# PCB_1.net
KiCad netlist of a schematic drawn in EAGLE
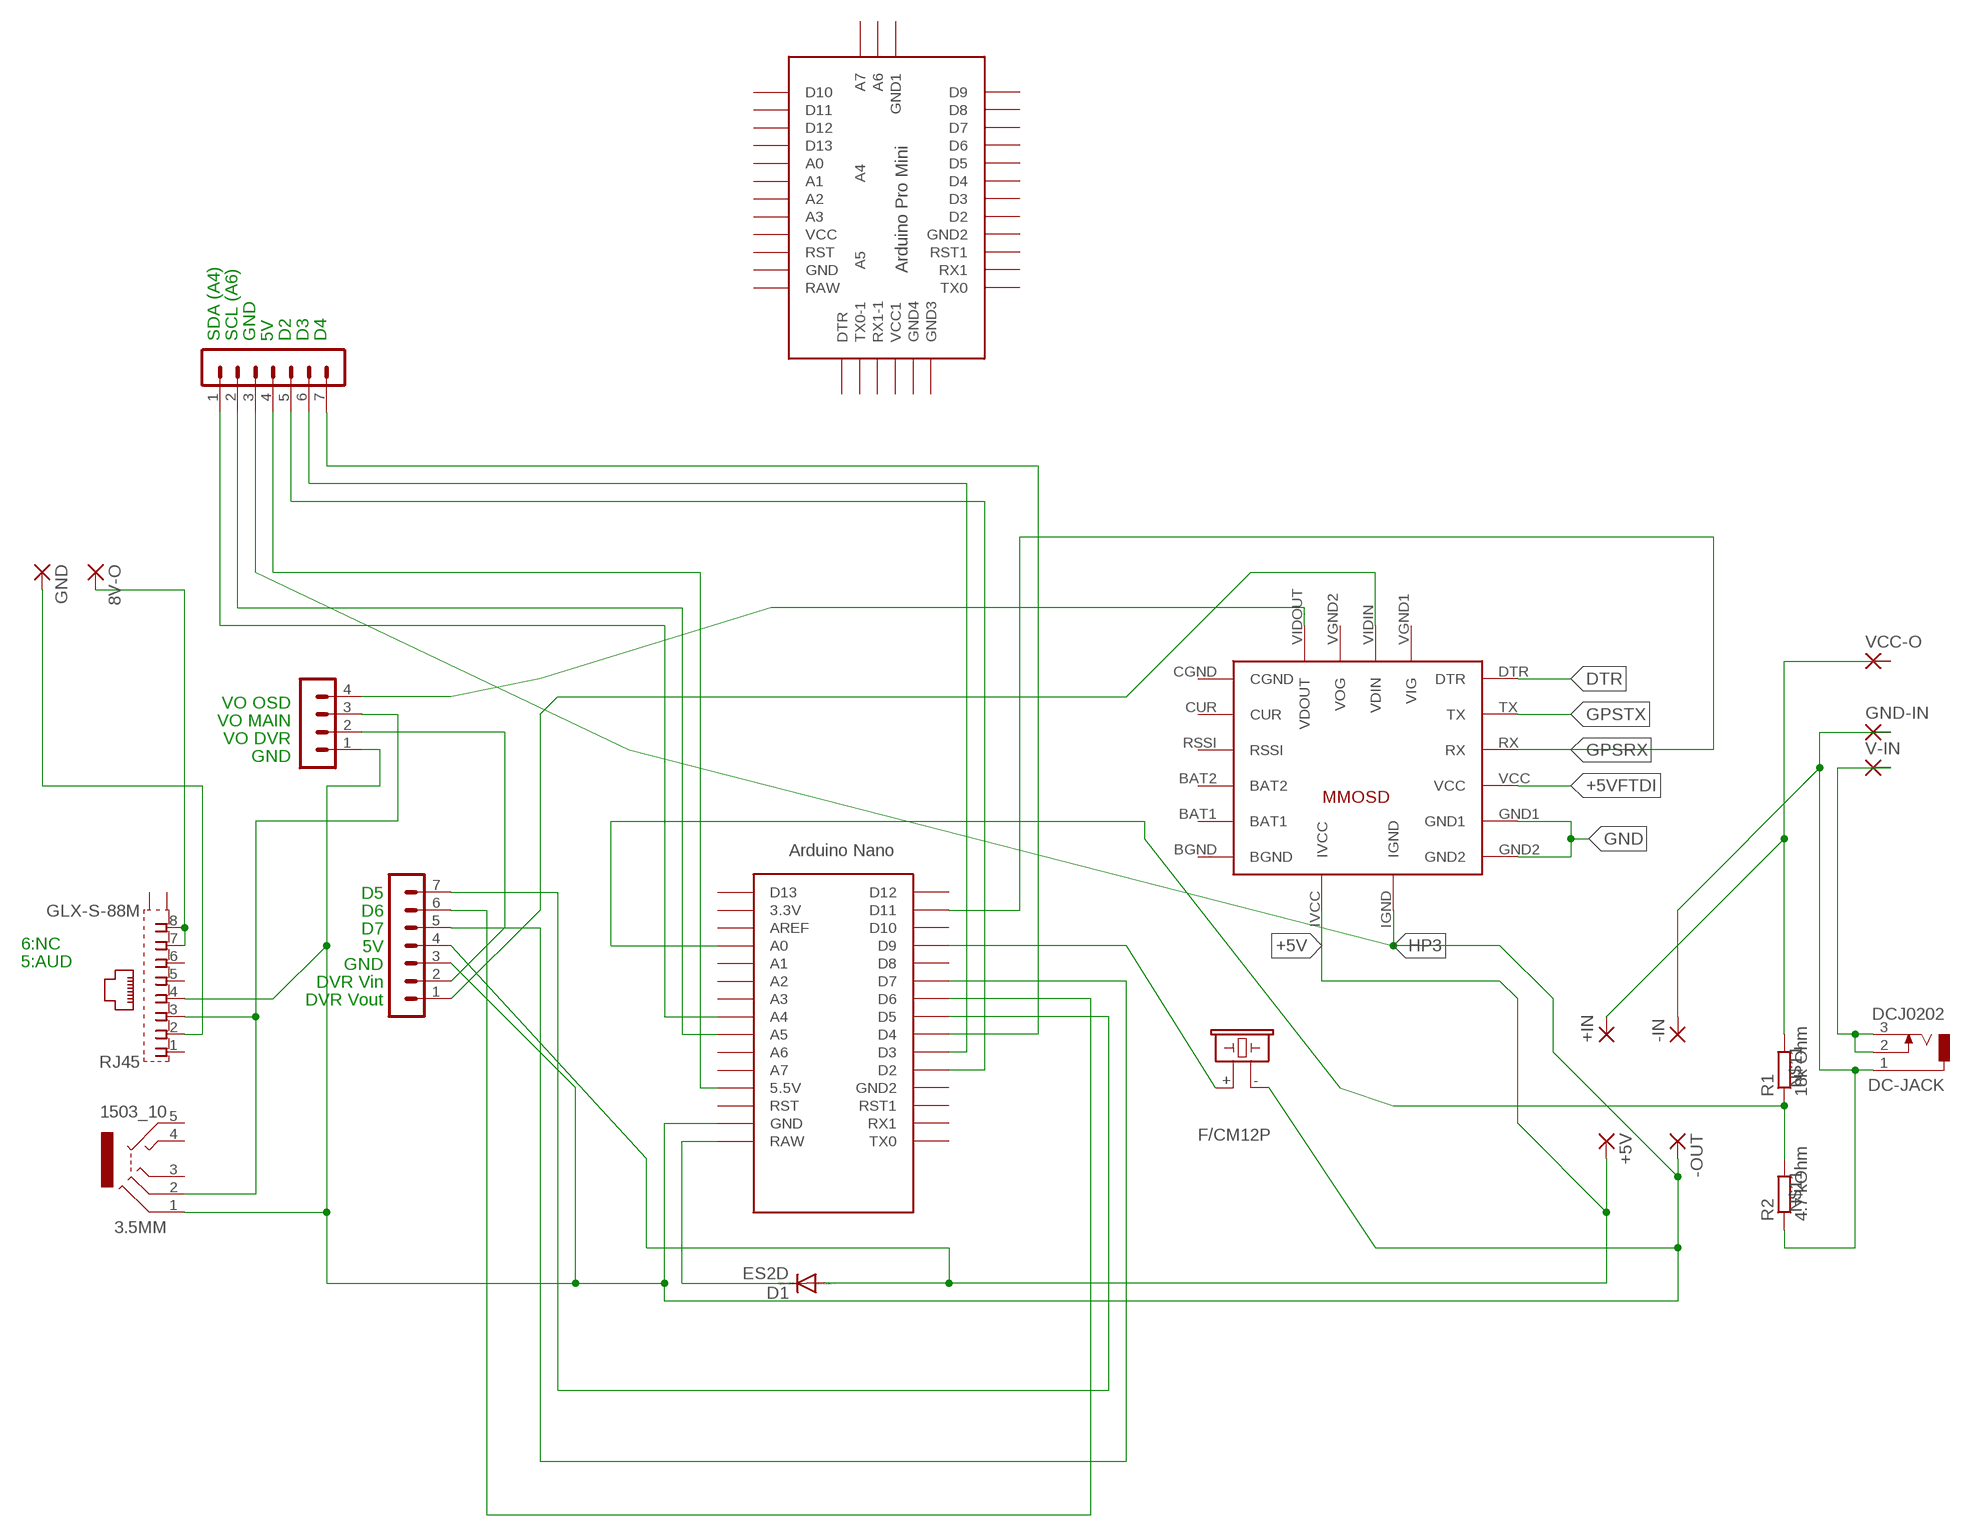
[diagram p0: schematic, sheet 1]

(export (version "E")
  (design (tool "Eeschema 10.0.6"))
  (components
    (comp (ref "+5V")
      (value "SMD2")
      (footprint "eagle-import:SMD1,27-2,54")
      (libsource (lib "eagle-import") (part "SMD2"))
    )
    (comp (ref "+IN")
      (value "SMD2")
      (footprint "eagle-import:SMD1,27-2,54")
      (libsource (lib "eagle-import") (part "SMD2"))
    )
    (comp (ref "-IN")
      (value "SMD2")
      (footprint "eagle-import:SMD1,27-2,54")
      (libsource (lib "eagle-import") (part "SMD2"))
    )
    (comp (ref "-OUT")
      (value "SMD2")
      (footprint "eagle-import:SMD1,27-2,54")
      (libsource (lib "eagle-import") (part "SMD2"))
    )
    (comp (ref "3.5MM")
      (value "1503_10")
      (footprint "eagle-import:1503_10")
      (libsource (lib "eagle-import") (part "1503_10"))
    )
    (comp (ref "8V-O")
      (value "2,54/1,1")
      (footprint "eagle-import:2,54_1,1")
      (libsource (lib "eagle-import") (part "2,54/1,1"))
    )
    (comp (ref "ADRUINO-NANO")
      (value "NANOB")
      (footprint "eagle-import:NANO")
      (libsource (lib "eagle-import") (part "NANOB"))
    )
    (comp (ref "BUZZ")
      (value "F/CM12P")
      (footprint "eagle-import:F_CM12P")
      (fields (field (name "SPICEPREFIX") "X"))
      (libsource (lib "eagle-import") (part "F/CM12P"))
    )
    (comp (ref "D1")
      (value "ES2D")
      (footprint "eagle-import:SMB")
      (libsource (lib "eagle-import") (part "ES2D"))
    )
    (comp (ref "DC-JACK")
      (value "DCJ0202")
      (footprint "eagle-import:DCJ0202")
      (libsource (lib "eagle-import") (part "DCJ0202"))
    )
    (comp (ref "GND")
      (value "2,54/1,1")
      (footprint "eagle-import:2,54_1,1")
      (libsource (lib "eagle-import") (part "2,54/1,1"))
    )
    (comp (ref "GND-IN")
      (value "2,54/1,1")
      (footprint "eagle-import:2,54_1,1")
      (libsource (lib "eagle-import") (part "2,54/1,1"))
    )
    (comp (ref "IO1")
      (value "MA07-1")
      (footprint "eagle-import:MA07-1")
      (libsource (lib "eagle-import") (part "MA07-1"))
    )
    (comp (ref "IO2")
      (value "MA07-1")
      (footprint "eagle-import:MA07-1")
      (libsource (lib "eagle-import") (part "MA07-1"))
    )
    (comp (ref "IO3")
      (value "MA04-1")
      (footprint "eagle-import:MA04-1")
      (libsource (lib "eagle-import") (part "MA04-1"))
    )
    (comp (ref "MINIMOSD")
      (value "MICROMINIMOSDPWR")
      (footprint "eagle-import:MMOSDNVDVID")
      (libsource (lib "eagle-import") (part "MICROMINIMOSDPWR"))
    )
    (comp (ref "R1")
      (value "18k Ohm")
      (footprint "eagle-import:M1206")
      (libsource (lib "eagle-import") (part "R-EU_M1206"))
    )
    (comp (ref "R2")
      (value "4.7 kOhm")
      (footprint "eagle-import:M1206")
      (libsource (lib "eagle-import") (part "R-EU_M1206"))
    )
    (comp (ref "RJ45")
      (value "GLX-S-88M")
      (footprint "eagle-import:GLX-S-88M")
      (libsource (lib "eagle-import") (part "GLX-S-88M"))
    )
    (comp (ref "U$1")
      (value "ABK-PRO-MINI")
      (footprint "eagle-import:ABK-PRO-MINI")
      (libsource (lib "eagle-import") (part "ABK-PRO-MINI"))
    )
    (comp (ref "V-IN")
      (value "2,54/1,1")
      (footprint "eagle-import:2,54_1,1")
      (libsource (lib "eagle-import") (part "2,54/1,1"))
    )
    (comp (ref "VCC-O")
      (value "2,54/1,1")
      (footprint "eagle-import:2,54_1,1")
      (libsource (lib "eagle-import") (part "2,54/1,1"))
    )
  )
  (nets
    (net (code "1") (name "+5V") (class "Default")
      (node (ref "+5V") (pin "1") (pinfunction "P_1") (pintype "passive"))
      (node (ref "D1") (pin "A") (pinfunction "A_A") (pintype "passive"))
      (node (ref "IO1") (pin "4") (pinfunction "4_4") (pintype "passive"))
      (node (ref "MINIMOSD") (pin "IVCC") (pinfunction "IVCC_IVCC") (pintype "power_in"))
    )
    (net (code "2") (name "+5VFTDI") (class "Default")
      (node (ref "MINIMOSD") (pin "VCC") (pinfunction "VCC_VCC") (pintype "power_in"))
    )
    (net (code "3") (name "/BAT1") (class "Default")
      (node (ref "MINIMOSD") (pin "BAT1") (pinfunction "BAT1_BAT1") (pintype "power_in"))
    )
    (net (code "4") (name "/BAT2") (class "Default")
      (node (ref "MINIMOSD") (pin "BAT2") (pinfunction "BAT2_BAT2") (pintype "power_in"))
    )
    (net (code "5") (name "/BGND") (class "Default")
      (node (ref "MINIMOSD") (pin "BGND") (pinfunction "BGND_BGND") (pintype "power_in"))
    )
    (net (code "6") (name "/CGND") (class "Default")
      (node (ref "MINIMOSD") (pin "CGND") (pinfunction "CGND_CGND") (pintype "power_in"))
    )
    (net (code "7") (name "/N$11") (class "Default")
      (node (ref "-IN") (pin "1") (pinfunction "P_1") (pintype "passive"))
      (node (ref "DC-JACK") (pin "1") (pinfunction "1_1") (pintype "passive"))
      (node (ref "GND-IN") (pin "1") (pinfunction "P_1") (pintype "passive"))
      (node (ref "R2") (pin "1") (pinfunction "1_1") (pintype "passive"))
    )
    (net (code "8") (name "DTR") (class "Default")
      (node (ref "MINIMOSD") (pin "DTR") (pinfunction "DTR_DTR") (pintype "bidirectional"))
    )
    (net (code "9") (name "GND") (class "Default")
      (node (ref "MINIMOSD") (pin "GND1") (pinfunction "GND1_GND1") (pintype "power_in"))
      (node (ref "MINIMOSD") (pin "GND2") (pinfunction "GND2_GND2") (pintype "power_in"))
    )
    (net (code "10") (name "GPSRX") (class "Default")
      (node (ref "ADRUINO-NANO") (pin "D11") (pinfunction "D11_D11") (pintype "bidirectional"))
      (node (ref "MINIMOSD") (pin "RX") (pinfunction "RX_RX") (pintype "input"))
    )
    (net (code "11") (name "GPSTX") (class "Default")
      (node (ref "MINIMOSD") (pin "TX") (pinfunction "TX_TX") (pintype "output"))
    )
    (net (code "12") (name "HP3") (class "Default")
      (node (ref "-OUT") (pin "1") (pinfunction "P_1") (pintype "passive"))
      (node (ref "3.5MM") (pin "1") (pinfunction "1_1") (pintype "passive"))
      (node (ref "ADRUINO-NANO") (pin "GND") (pinfunction "GND_GND") (pintype "bidirectional"))
      (node (ref "BUZZ") (pin "-") (pinfunction "2_-") (pintype "passive"))
      (node (ref "IO1") (pin "3") (pinfunction "3_3") (pintype "passive"))
      (node (ref "IO2") (pin "3") (pinfunction "3_3") (pintype "passive"))
      (node (ref "IO3") (pin "1") (pinfunction "1_1") (pintype "passive"))
      (node (ref "MINIMOSD") (pin "IGND") (pinfunction "IGND_IGND") (pintype "power_in"))
      (node (ref "RJ45") (pin "4") (pinfunction "4_4") (pintype "passive"))
    )
    (net (code "13") (name "Net-(+IN-P)") (class "Default")
      (node (ref "+IN") (pin "1") (pinfunction "P_1") (pintype "passive"))
      (node (ref "R1") (pin "2") (pinfunction "2_2") (pintype "passive"))
      (node (ref "VCC-O") (pin "1") (pinfunction "P_1") (pintype "passive"))
    )
    (net (code "14") (name "Net-(3.5MM-Pad2)") (class "Default")
      (node (ref "3.5MM") (pin "2") (pinfunction "2_2") (pintype "passive"))
      (node (ref "IO3") (pin "3") (pinfunction "3_3") (pintype "passive"))
      (node (ref "RJ45") (pin "3") (pinfunction "3_3") (pintype "passive"))
    )
    (net (code "15") (name "Net-(8V-O-P)") (class "Default")
      (node (ref "8V-O") (pin "1") (pinfunction "P_1") (pintype "passive"))
      (node (ref "RJ45") (pin "7") (pinfunction "7_7") (pintype "passive"))
      (node (ref "RJ45") (pin "8") (pinfunction "8_8") (pintype "passive"))
    )
    (net (code "16") (name "Net-(ADRUINO-NANO-5.5V)") (class "Default")
      (node (ref "ADRUINO-NANO") (pin "5V") (pinfunction "5.5V_5V") (pintype "bidirectional"))
      (node (ref "IO2") (pin "4") (pinfunction "4_4") (pintype "passive"))
    )
    (net (code "17") (name "Net-(ADRUINO-NANO-PadA0)") (class "Default")
      (node (ref "ADRUINO-NANO") (pin "A0") (pinfunction "A0_A0") (pintype "bidirectional"))
      (node (ref "R1") (pin "1") (pinfunction "1_1") (pintype "passive"))
      (node (ref "R2") (pin "2") (pinfunction "2_2") (pintype "passive"))
    )
    (net (code "18") (name "Net-(ADRUINO-NANO-PadA4)") (class "Default")
      (node (ref "ADRUINO-NANO") (pin "A4") (pinfunction "A4_A4") (pintype "bidirectional"))
      (node (ref "IO2") (pin "1") (pinfunction "1_1") (pintype "passive"))
    )
    (net (code "19") (name "Net-(ADRUINO-NANO-PadA5)") (class "Default")
      (node (ref "ADRUINO-NANO") (pin "A5") (pinfunction "A5_A5") (pintype "bidirectional"))
      (node (ref "IO2") (pin "2") (pinfunction "2_2") (pintype "passive"))
    )
    (net (code "20") (name "Net-(ADRUINO-NANO-PadD2)") (class "Default")
      (node (ref "ADRUINO-NANO") (pin "D2") (pinfunction "D2_D2") (pintype "bidirectional"))
      (node (ref "IO2") (pin "5") (pinfunction "5_5") (pintype "passive"))
    )
    (net (code "21") (name "Net-(ADRUINO-NANO-PadD3)") (class "Default")
      (node (ref "ADRUINO-NANO") (pin "D3") (pinfunction "D3_D3") (pintype "bidirectional"))
      (node (ref "IO2") (pin "6") (pinfunction "6_6") (pintype "passive"))
    )
    (net (code "22") (name "Net-(ADRUINO-NANO-PadD4)") (class "Default")
      (node (ref "ADRUINO-NANO") (pin "D4") (pinfunction "D4_D4") (pintype "bidirectional"))
      (node (ref "IO2") (pin "7") (pinfunction "7_7") (pintype "passive"))
    )
    (net (code "23") (name "Net-(ADRUINO-NANO-PadD5)") (class "Default")
      (node (ref "ADRUINO-NANO") (pin "D5") (pinfunction "D5_D5") (pintype "bidirectional"))
      (node (ref "IO1") (pin "7") (pinfunction "7_7") (pintype "passive"))
    )
    (net (code "24") (name "Net-(ADRUINO-NANO-PadD6)") (class "Default")
      (node (ref "ADRUINO-NANO") (pin "D6") (pinfunction "D6_D6") (pintype "bidirectional"))
      (node (ref "IO1") (pin "6") (pinfunction "6_6") (pintype "passive"))
    )
    (net (code "25") (name "Net-(ADRUINO-NANO-PadD7)") (class "Default")
      (node (ref "ADRUINO-NANO") (pin "D7") (pinfunction "D7_D7") (pintype "bidirectional"))
      (node (ref "IO1") (pin "5") (pinfunction "5_5") (pintype "passive"))
    )
    (net (code "26") (name "Net-(ADRUINO-NANO-PadRAW)") (class "Default")
      (node (ref "ADRUINO-NANO") (pin "RAW") (pinfunction "RAW_RAW") (pintype "bidirectional"))
      (node (ref "D1") (pin "C") (pinfunction "C_C") (pintype "passive"))
    )
    (net (code "27") (name "Net-(BUZZ-1)") (class "Default")
      (node (ref "ADRUINO-NANO") (pin "D9") (pinfunction "D9_D9") (pintype "bidirectional"))
      (node (ref "BUZZ") (pin "+") (pinfunction "1_+") (pintype "passive"))
    )
    (net (code "28") (name "Net-(GND-P)") (class "Default")
      (node (ref "GND") (pin "1") (pinfunction "P_1") (pintype "passive"))
      (node (ref "RJ45") (pin "2") (pinfunction "2_2") (pintype "passive"))
    )
    (net (code "29") (name "Net-(IO1-Pad2)") (class "Default")
      (node (ref "IO1") (pin "2") (pinfunction "2_2") (pintype "passive"))
      (node (ref "IO3") (pin "2") (pinfunction "2_2") (pintype "passive"))
    )
    (net (code "30") (name "Net-(MINIMOSD-VDIN)") (class "Default")
      (node (ref "IO1") (pin "1") (pinfunction "1_1") (pintype "passive"))
      (node (ref "MINIMOSD") (pin "VIDIN") (pinfunction "VDIN_VIDIN") (pintype "input"))
    )
    (net (code "31") (name "Net-(MINIMOSD-VDOUT)") (class "Default")
      (node (ref "IO3") (pin "4") (pinfunction "4_4") (pintype "passive"))
      (node (ref "MINIMOSD") (pin "VIDOUT") (pinfunction "VDOUT_VIDOUT") (pintype "output"))
    )
    (net (code "32") (name "Net-(V-IN-P)") (class "Default")
      (node (ref "DC-JACK") (pin "2") (pinfunction "2_2") (pintype "passive"))
      (node (ref "DC-JACK") (pin "3") (pinfunction "3_3") (pintype "passive"))
      (node (ref "V-IN") (pin "1") (pinfunction "P_1") (pintype "passive"))
    )
    (net (code "33") (name "unconnected-(3.5MM-Pad3)") (class "Default")
      (node (ref "3.5MM") (pin "3") (pinfunction "3_3") (pintype "passive"))
    )
    (net (code "34") (name "unconnected-(3.5MM-Pad4)") (class "Default")
      (node (ref "3.5MM") (pin "4") (pinfunction "4_4") (pintype "passive"))
    )
    (net (code "35") (name "unconnected-(3.5MM-Pad5)") (class "Default")
      (node (ref "3.5MM") (pin "5") (pinfunction "5_5") (pintype "passive"))
    )
    (net (code "36") (name "unconnected-(ADRUINO-NANO-GND2-PadGND1)") (class "Default")
      (node (ref "ADRUINO-NANO") (pin "GND1") (pinfunction "GND2_GND1") (pintype "bidirectional"))
    )
    (net (code "37") (name "unconnected-(ADRUINO-NANO-Pad3.3V)") (class "Default")
      (node (ref "ADRUINO-NANO") (pin "3.3V") (pinfunction "3.3V_3.3V") (pintype "bidirectional"))
    )
    (net (code "38") (name "unconnected-(ADRUINO-NANO-PadA1)") (class "Default")
      (node (ref "ADRUINO-NANO") (pin "A1") (pinfunction "A1_A1") (pintype "bidirectional"))
    )
    (net (code "39") (name "unconnected-(ADRUINO-NANO-PadA2)") (class "Default")
      (node (ref "ADRUINO-NANO") (pin "A2") (pinfunction "A2_A2") (pintype "bidirectional"))
    )
    (net (code "40") (name "unconnected-(ADRUINO-NANO-PadA3)") (class "Default")
      (node (ref "ADRUINO-NANO") (pin "A3") (pinfunction "A3_A3") (pintype "bidirectional"))
    )
    (net (code "41") (name "unconnected-(ADRUINO-NANO-PadA6)") (class "Default")
      (node (ref "ADRUINO-NANO") (pin "A6") (pinfunction "A6_A6") (pintype "bidirectional"))
    )
    (net (code "42") (name "unconnected-(ADRUINO-NANO-PadA7)") (class "Default")
      (node (ref "ADRUINO-NANO") (pin "A7") (pinfunction "A7_A7") (pintype "bidirectional"))
    )
    (net (code "43") (name "unconnected-(ADRUINO-NANO-PadAREF)") (class "Default")
      (node (ref "ADRUINO-NANO") (pin "AREF") (pinfunction "AREF_AREF") (pintype "bidirectional"))
    )
    (net (code "44") (name "unconnected-(ADRUINO-NANO-PadD8)") (class "Default")
      (node (ref "ADRUINO-NANO") (pin "D8") (pinfunction "D8_D8") (pintype "bidirectional"))
    )
    (net (code "45") (name "unconnected-(ADRUINO-NANO-PadD10)") (class "Default")
      (node (ref "ADRUINO-NANO") (pin "D10") (pinfunction "D10_D10") (pintype "bidirectional"))
    )
    (net (code "46") (name "unconnected-(ADRUINO-NANO-PadD12)") (class "Default")
      (node (ref "ADRUINO-NANO") (pin "D12") (pinfunction "D12_D12") (pintype "bidirectional"))
    )
    (net (code "47") (name "unconnected-(ADRUINO-NANO-PadD13)") (class "Default")
      (node (ref "ADRUINO-NANO") (pin "D13") (pinfunction "D13_D13") (pintype "bidirectional"))
    )
    (net (code "48") (name "unconnected-(ADRUINO-NANO-PadRST)") (class "Default")
      (node (ref "ADRUINO-NANO") (pin "RST") (pinfunction "RST_RST") (pintype "bidirectional"))
    )
    (net (code "49") (name "unconnected-(ADRUINO-NANO-PadRST1)") (class "Default")
      (node (ref "ADRUINO-NANO") (pin "RST1") (pinfunction "RST1_RST1") (pintype "bidirectional"))
    )
    (net (code "50") (name "unconnected-(ADRUINO-NANO-PadRX1)") (class "Default")
      (node (ref "ADRUINO-NANO") (pin "RX1") (pinfunction "RX1_RX1") (pintype "bidirectional"))
    )
    (net (code "51") (name "unconnected-(ADRUINO-NANO-PadTX0)") (class "Default")
      (node (ref "ADRUINO-NANO") (pin "TX0") (pinfunction "TX0_TX0") (pintype "bidirectional"))
    )
    (net (code "52") (name "unconnected-(MINIMOSD-PadCUR)") (class "Default")
      (node (ref "MINIMOSD") (pin "CUR") (pinfunction "CUR_CUR") (pintype "bidirectional"))
    )
    (net (code "53") (name "unconnected-(MINIMOSD-PadRSSI)") (class "Default")
      (node (ref "MINIMOSD") (pin "RSSI") (pinfunction "RSSI_RSSI") (pintype "bidirectional"))
    )
    (net (code "54") (name "unconnected-(MINIMOSD-VIG-PadVGND1)") (class "Default")
      (node (ref "MINIMOSD") (pin "VGND1") (pinfunction "VIG_VGND1") (pintype "input"))
    )
    (net (code "55") (name "unconnected-(MINIMOSD-VOG-PadVGND2)") (class "Default")
      (node (ref "MINIMOSD") (pin "VGND2") (pinfunction "VOG_VGND2") (pintype "output"))
    )
    (net (code "56") (name "unconnected-(RJ45-Pad1)") (class "Default")
      (node (ref "RJ45") (pin "1") (pinfunction "1_1") (pintype "passive"))
    )
    (net (code "57") (name "unconnected-(RJ45-Pad5)") (class "Default")
      (node (ref "RJ45") (pin "5") (pinfunction "5_5") (pintype "passive"))
    )
    (net (code "58") (name "unconnected-(RJ45-Pad6)") (class "Default")
      (node (ref "RJ45") (pin "6") (pinfunction "6_6") (pintype "passive"))
    )
    (net (code "59") (name "unconnected-(RJ45-PadS1)") (class "Default")
      (node (ref "RJ45") (pin "S1") (pinfunction "S1_S1") (pintype "passive"))
    )
    (net (code "60") (name "unconnected-(RJ45-PadS2)") (class "Default")
      (node (ref "RJ45") (pin "S2") (pinfunction "S2_S2") (pintype "passive"))
    )
    (net (code "61") (name "unconnected-(U$1-GND1-PadGND4)") (class "Default")
      (node (ref "U$1") (pin "GND4") (pinfunction "GND1_GND4") (pintype "bidirectional"))
    )
    (net (code "62") (name "unconnected-(U$1-GND2-PadGND1)") (class "Default")
      (node (ref "U$1") (pin "GND1") (pinfunction "GND2_GND1") (pintype "bidirectional"))
    )
    (net (code "63") (name "unconnected-(U$1-GND3-PadGND2)") (class "Default")
      (node (ref "U$1") (pin "GND2") (pinfunction "GND3_GND2") (pintype "bidirectional"))
    )
    (net (code "64") (name "unconnected-(U$1-GND4-PadGND3)") (class "Default")
      (node (ref "U$1") (pin "GND3") (pinfunction "GND4_GND3") (pintype "bidirectional"))
    )
    (net (code "65") (name "unconnected-(U$1-PadA0)") (class "Default")
      (node (ref "U$1") (pin "A0") (pinfunction "A0_A0") (pintype "bidirectional"))
    )
    (net (code "66") (name "unconnected-(U$1-PadA1)") (class "Default")
      (node (ref "U$1") (pin "A1") (pinfunction "A1_A1") (pintype "bidirectional"))
    )
    (net (code "67") (name "unconnected-(U$1-PadA2)") (class "Default")
      (node (ref "U$1") (pin "A2") (pinfunction "A2_A2") (pintype "bidirectional"))
    )
    (net (code "68") (name "unconnected-(U$1-PadA3)") (class "Default")
      (node (ref "U$1") (pin "A3") (pinfunction "A3_A3") (pintype "bidirectional"))
    )
    (net (code "69") (name "unconnected-(U$1-PadA4)") (class "Default")
      (node (ref "U$1") (pin "A4") (pinfunction "A4_A4") (pintype "bidirectional"))
    )
    (net (code "70") (name "unconnected-(U$1-PadA5)") (class "Default")
      (node (ref "U$1") (pin "A5") (pinfunction "A5_A5") (pintype "bidirectional"))
    )
    (net (code "71") (name "unconnected-(U$1-PadA6)") (class "Default")
      (node (ref "U$1") (pin "A6") (pinfunction "A6_A6") (pintype "bidirectional"))
    )
    (net (code "72") (name "unconnected-(U$1-PadA7)") (class "Default")
      (node (ref "U$1") (pin "A7") (pinfunction "A7_A7") (pintype "bidirectional"))
    )
    (net (code "73") (name "unconnected-(U$1-PadD2)") (class "Default")
      (node (ref "U$1") (pin "D2") (pinfunction "D2_D2") (pintype "bidirectional"))
    )
    (net (code "74") (name "unconnected-(U$1-PadD3)") (class "Default")
      (node (ref "U$1") (pin "D3") (pinfunction "D3_D3") (pintype "bidirectional"))
    )
    (net (code "75") (name "unconnected-(U$1-PadD4)") (class "Default")
      (node (ref "U$1") (pin "D4") (pinfunction "D4_D4") (pintype "bidirectional"))
    )
    (net (code "76") (name "unconnected-(U$1-PadD5)") (class "Default")
      (node (ref "U$1") (pin "D5") (pinfunction "D5_D5") (pintype "bidirectional"))
    )
    (net (code "77") (name "unconnected-(U$1-PadD6)") (class "Default")
      (node (ref "U$1") (pin "D6") (pinfunction "D6_D6") (pintype "bidirectional"))
    )
    (net (code "78") (name "unconnected-(U$1-PadD7)") (class "Default")
      (node (ref "U$1") (pin "D7") (pinfunction "D7_D7") (pintype "bidirectional"))
    )
    (net (code "79") (name "unconnected-(U$1-PadD8)") (class "Default")
      (node (ref "U$1") (pin "D8") (pinfunction "D8_D8") (pintype "bidirectional"))
    )
    (net (code "80") (name "unconnected-(U$1-PadD9)") (class "Default")
      (node (ref "U$1") (pin "D9") (pinfunction "D9_D9") (pintype "bidirectional"))
    )
    (net (code "81") (name "unconnected-(U$1-PadD10)") (class "Default")
      (node (ref "U$1") (pin "D10") (pinfunction "D10_D10") (pintype "bidirectional"))
    )
    (net (code "82") (name "unconnected-(U$1-PadD11)") (class "Default")
      (node (ref "U$1") (pin "D11") (pinfunction "D11_D11") (pintype "bidirectional"))
    )
    (net (code "83") (name "unconnected-(U$1-PadD12)") (class "Default")
      (node (ref "U$1") (pin "D12") (pinfunction "D12_D12") (pintype "bidirectional"))
    )
    (net (code "84") (name "unconnected-(U$1-PadD13)") (class "Default")
      (node (ref "U$1") (pin "D13") (pinfunction "D13_D13") (pintype "bidirectional"))
    )
    (net (code "85") (name "unconnected-(U$1-PadDTR)") (class "Default")
      (node (ref "U$1") (pin "DTR") (pinfunction "DTR_DTR") (pintype "bidirectional"))
    )
    (net (code "86") (name "unconnected-(U$1-PadGND)") (class "Default")
      (node (ref "U$1") (pin "GND") (pinfunction "GND_GND") (pintype "bidirectional"))
    )
    (net (code "87") (name "unconnected-(U$1-PadRAW)") (class "Default")
      (node (ref "U$1") (pin "RAW") (pinfunction "RAW_RAW") (pintype "bidirectional"))
    )
    (net (code "88") (name "unconnected-(U$1-PadRST)") (class "Default")
      (node (ref "U$1") (pin "RST") (pinfunction "RST_RST") (pintype "bidirectional"))
    )
    (net (code "89") (name "unconnected-(U$1-PadRST1)") (class "Default")
      (node (ref "U$1") (pin "RST1") (pinfunction "RST1_RST1") (pintype "bidirectional"))
    )
    (net (code "90") (name "unconnected-(U$1-PadRX1)") (class "Default")
      (node (ref "U$1") (pin "RX1") (pinfunction "RX1_RX1") (pintype "bidirectional"))
    )
    (net (code "91") (name "unconnected-(U$1-PadRX1-1)") (class "Default")
      (node (ref "U$1") (pin "RX1-1") (pinfunction "RX1-1_RX1-1") (pintype "bidirectional"))
    )
    (net (code "92") (name "unconnected-(U$1-PadTX0)") (class "Default")
      (node (ref "U$1") (pin "TX0") (pinfunction "TX0_TX0") (pintype "bidirectional"))
    )
    (net (code "93") (name "unconnected-(U$1-PadTX0-1)") (class "Default")
      (node (ref "U$1") (pin "TX0-1") (pinfunction "TX0-1_TX0-1") (pintype "bidirectional"))
    )
    (net (code "94") (name "unconnected-(U$1-PadVCC)") (class "Default")
      (node (ref "U$1") (pin "VCC") (pinfunction "VCC_VCC") (pintype "bidirectional"))
    )
    (net (code "95") (name "unconnected-(U$1-PadVCC1)") (class "Default")
      (node (ref "U$1") (pin "VCC1") (pinfunction "VCC1_VCC1") (pintype "bidirectional"))
    )
  )
)
